# Sheet1.net
KiCad netlist of a schematic drawn in Altium Designer
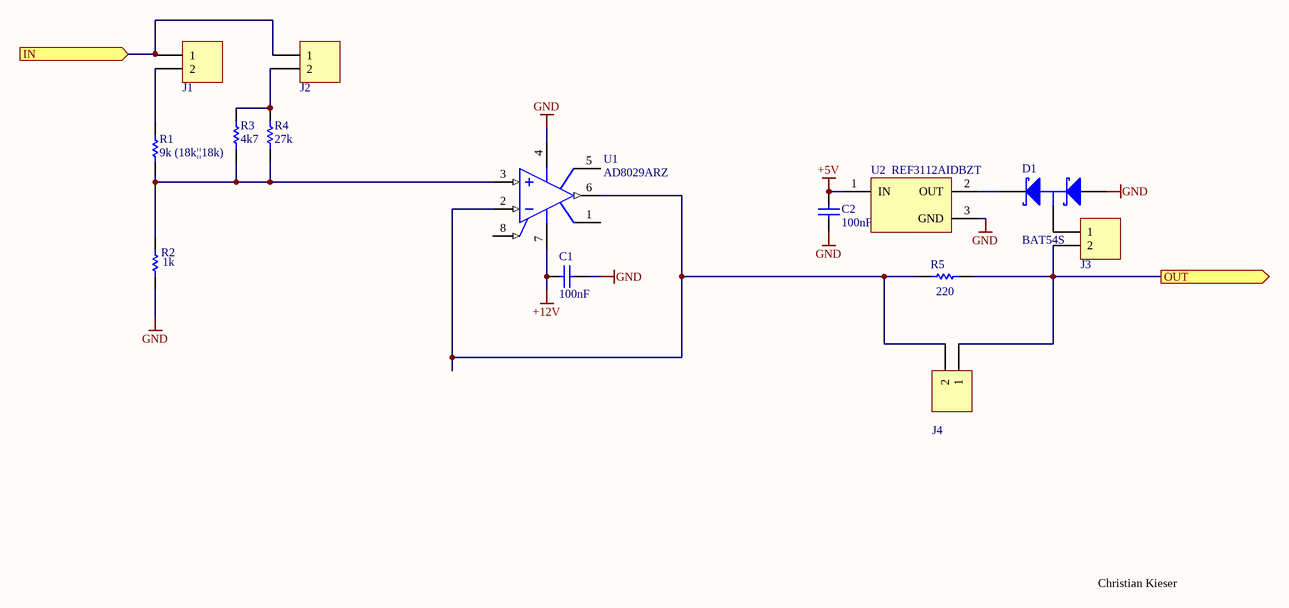
[diagram p0: Sheet1.SchDoc]

(export (version "E")
  (design (tool "Eeschema 10.0.6"))
  (components
    (comp (ref "C1")
      (value "100nF")
      (footprint "CAPC2013X88X50ML20T25")
      (description "generic 0805 COG oder X7R Vielschichtkondensatoren max. +/-10%")
      (libsource (lib "Altium Vault EMBL") (part "CMP-001-0082-2"))
    )
    (comp (ref "C2")
      (value "100nF")
      (footprint "CAPC2013X88X50ML20T25")
      (description "generic 0805 COG oder X7R Vielschichtkondensatoren max. +/-10%")
      (libsource (lib "Altium Vault EMBL") (part "CMP-001-0082-2"))
    )
    (comp (ref "D1")
      (value "BAT54S")
      (footprint "FAIR-SOT23-3_V")
      (description "Schottky Barrier Diode, 30 V, 0.2 A, -55 to 150 degC, 3-Pin SOT23, RoHS, Tape and Reel")
      (fields (field (name "TOLERANCE") "30ppm") (field (name "MANUFACTURER") "DIODES INC."))
      (libsource (lib "Altium Vault EMBL 3") (part "CMP-00532-3"))
    )
    (comp (ref "J1")
      (value "61300211121")
      (footprint "61300211121")
      (description "2Pol; gerade; WR-PHD 2.54 mm THT Pin Header")
      (fields (field (name "MANUFACTURER") "Wurth Electronics"))
      (libsource (lib "Altium Vault EMBL 3") (part "CMP-001-0071-1"))
    )
    (comp (ref "J2")
      (value "61300211121")
      (footprint "61300211121")
      (description "2Pol; gerade; WR-PHD 2.54 mm THT Pin Header")
      (fields (field (name "MANUFACTURER") "Wurth Electronics"))
      (libsource (lib "Altium Vault EMBL 3") (part "CMP-001-0071-1"))
    )
    (comp (ref "J3")
      (value "61300211121")
      (footprint "61300211121")
      (description "2Pol; gerade; WR-PHD 2.54 mm THT Pin Header")
      (fields (field (name "MANUFACTURER") "Wurth Electronics"))
      (libsource (lib "Altium Vault EMBL 3") (part "CMP-001-0071-1"))
    )
    (comp (ref "J4")
      (value "61300211121")
      (footprint "61300211121")
      (description "2Pol; gerade; WR-PHD 2.54 mm THT Pin Header")
      (fields (field (name "MANUFACTURER") "Wurth Electronics"))
      (libsource (lib "") (part "CMP-001-0071-1_1"))
    )
    (comp (ref "R1")
      (value "9k (18kΖ18k)")
      (footprint "YAGO-RC0805_M")
      (description "0805 Yageo Standard BlackBox Resistors")
      (fields (field (name "TOLERANCE") "±1%") (field (name "MANUFACTURER") "Yageo"))
      (libsource (lib "Altium Vault EMBL") (part "CMP-001-0027-2"))
    )
    (comp (ref "R2")
      (value "1k")
      (footprint "YAGO-RC0805_M")
      (description "0805 Yageo Standard BlackBox Resistors")
      (fields (field (name "TOLERANCE") "±1%") (field (name "MANUFACTURER") "Yageo"))
      (libsource (lib "Altium Vault EMBL") (part "CMP-001-0027-2"))
    )
    (comp (ref "R3")
      (value "4k7")
      (footprint "YAGO-RC0805_M")
      (description "0805 Yageo Standard BlackBox Resistors")
      (fields (field (name "TOLERANCE") "±1%") (field (name "MANUFACTURER") "Yageo"))
      (libsource (lib "Altium Vault EMBL") (part "CMP-001-0027-2"))
    )
    (comp (ref "R4")
      (value "27k")
      (footprint "YAGO-RC0805_M")
      (description "0805 Yageo Standard BlackBox Resistors")
      (fields (field (name "TOLERANCE") "±1%") (field (name "MANUFACTURER") "Yageo"))
      (libsource (lib "Altium Vault EMBL") (part "CMP-001-0027-2"))
    )
    (comp (ref "R5")
      (value "220")
      (footprint "YAGO-RC0805_M")
      (description "0805 Yageo Standard BlackBox Resistors")
      (fields (field (name "TOLERANCE") "±1%") (field (name "MANUFACTURER") "Yageo"))
      (libsource (lib "Altium Vault EMBL") (part "CMP-001-0027-2"))
    )
    (comp (ref "U1")
      (value "AD8029ARZ")
      (footprint "ADI-R-8_L")
      (fields (field (name "MANUFACTURER") "Analog Devices") (field (name "GENERIC PART NUMBER") "AD8029"))
      (libsource (lib "Altium Vault EMBL 3") (part "CMP-00480-1"))
    )
    (comp (ref "U2")
      (value "REF3112AIDBZT")
      (footprint "DBZ0003A_N")
      (description "20 ppm / degC Max, 100 uA Series Voltage Reference, 3-pin SOT-23 (DBZ), Green (RoHS & no Sb/Br)")
      (fields (field (name "MANUFACTURER") "Texas Instruments"))
      (libsource (lib "Altium Vault EMBL 3") (part "CMP-00534-1"))
    )
  )
  (nets
    (net (code "1") (name "+5V") (class "Default")
      (node (ref "C2") (pin "1") (pinfunction "1_1") (pintype "passive"))
      (node (ref "U2") (pin "1") (pinfunction "IN_1") (pintype "power_in"))
    )
    (net (code "2") (name "+12V") (class "Default")
      (node (ref "C1") (pin "2") (pinfunction "2_2") (pintype "passive"))
      (node (ref "U1") (pin "7") (pinfunction "+VS_7") (pintype "power_in"))
    )
    (net (code "3") (name "/IN") (class "Default")
      (node (ref "J1") (pin "1") (pinfunction "1_1") (pintype "passive"))
      (node (ref "J2") (pin "1") (pinfunction "1_1") (pintype "passive"))
    )
    (net (code "4") (name "/OUT") (class "Default")
      (node (ref "J3") (pin "2") (pinfunction "2_2") (pintype "passive"))
      (node (ref "J4") (pin "1") (pinfunction "1_1") (pintype "passive"))
      (node (ref "R5") (pin "1") (pinfunction "1_1") (pintype "passive"))
    )
    (net (code "5") (name "GND") (class "Default")
      (node (ref "C1") (pin "1") (pinfunction "1_1") (pintype "passive"))
      (node (ref "C2") (pin "2") (pinfunction "2_2") (pintype "passive"))
      (node (ref "D1") (pin "1") (pinfunction "A_1") (pintype "passive"))
      (node (ref "R2") (pin "1") (pinfunction "1_1") (pintype "passive"))
      (node (ref "U1") (pin "4") (pinfunction "-VS_4") (pintype "power_in"))
      (node (ref "U2") (pin "3") (pinfunction "GND_3") (pintype "power_in"))
    )
    (net (code "6") (name "Net-(D1-C)") (class "Default")
      (node (ref "D1") (pin "3") (pinfunction "C_3") (pintype "passive"))
      (node (ref "J3") (pin "1") (pinfunction "1_1") (pintype "passive"))
    )
    (net (code "7") (name "Net-(D1-K)") (class "Default")
      (node (ref "D1") (pin "2") (pinfunction "K_2") (pintype "passive"))
      (node (ref "U2") (pin "2") (pinfunction "OUT_2") (pintype "power_in"))
    )
    (net (code "8") (name "Net-(J1-Pad2)") (class "Default")
      (node (ref "J1") (pin "2") (pinfunction "2_2") (pintype "passive"))
      (node (ref "R1") (pin "2") (pinfunction "2_2") (pintype "passive"))
    )
    (net (code "9") (name "Net-(J2-Pad2)") (class "Default")
      (node (ref "J2") (pin "2") (pinfunction "2_2") (pintype "passive"))
      (node (ref "R3") (pin "2") (pinfunction "2_2") (pintype "passive"))
      (node (ref "R4") (pin "2") (pinfunction "2_2") (pintype "passive"))
    )
    (net (code "10") (name "Net-(U1-+IN)") (class "Default")
      (node (ref "R1") (pin "1") (pinfunction "1_1") (pintype "passive"))
      (node (ref "R2") (pin "2") (pinfunction "2_2") (pintype "passive"))
      (node (ref "R3") (pin "1") (pinfunction "1_1") (pintype "passive"))
      (node (ref "R4") (pin "1") (pinfunction "1_1") (pintype "passive"))
      (node (ref "U1") (pin "3") (pinfunction "+IN_3") (pintype "input"))
    )
    (net (code "11") (name "Net-(U1--IN)") (class "Default")
      (node (ref "J4") (pin "2") (pinfunction "2_2") (pintype "passive"))
      (node (ref "R5") (pin "2") (pinfunction "2_2") (pintype "passive"))
      (node (ref "U1") (pin "2") (pinfunction "-IN_2") (pintype "input"))
      (node (ref "U1") (pin "6") (pinfunction "VOUT_6") (pintype "output"))
    )
    (net (code "12") (name "unconnected-(U1-NC-Pad1)") (class "Default")
      (node (ref "U1") (pin "1") (pinfunction "NC_1") (pintype "passive"))
    )
    (net (code "13") (name "unconnected-(U1-NC-Pad5)") (class "Default")
      (node (ref "U1") (pin "5") (pinfunction "NC_5") (pintype "passive"))
    )
    (net (code "14") (name "unconnected-(U1-~{DISABLE}-Pad8)") (class "Default")
      (node (ref "U1") (pin "8") (pinfunction "~{DISABLE}_8") (pintype "input"))
    )
  )
)
